# narvi-cpu.net
KiCad netlist of a schematic drawn in EAGLE
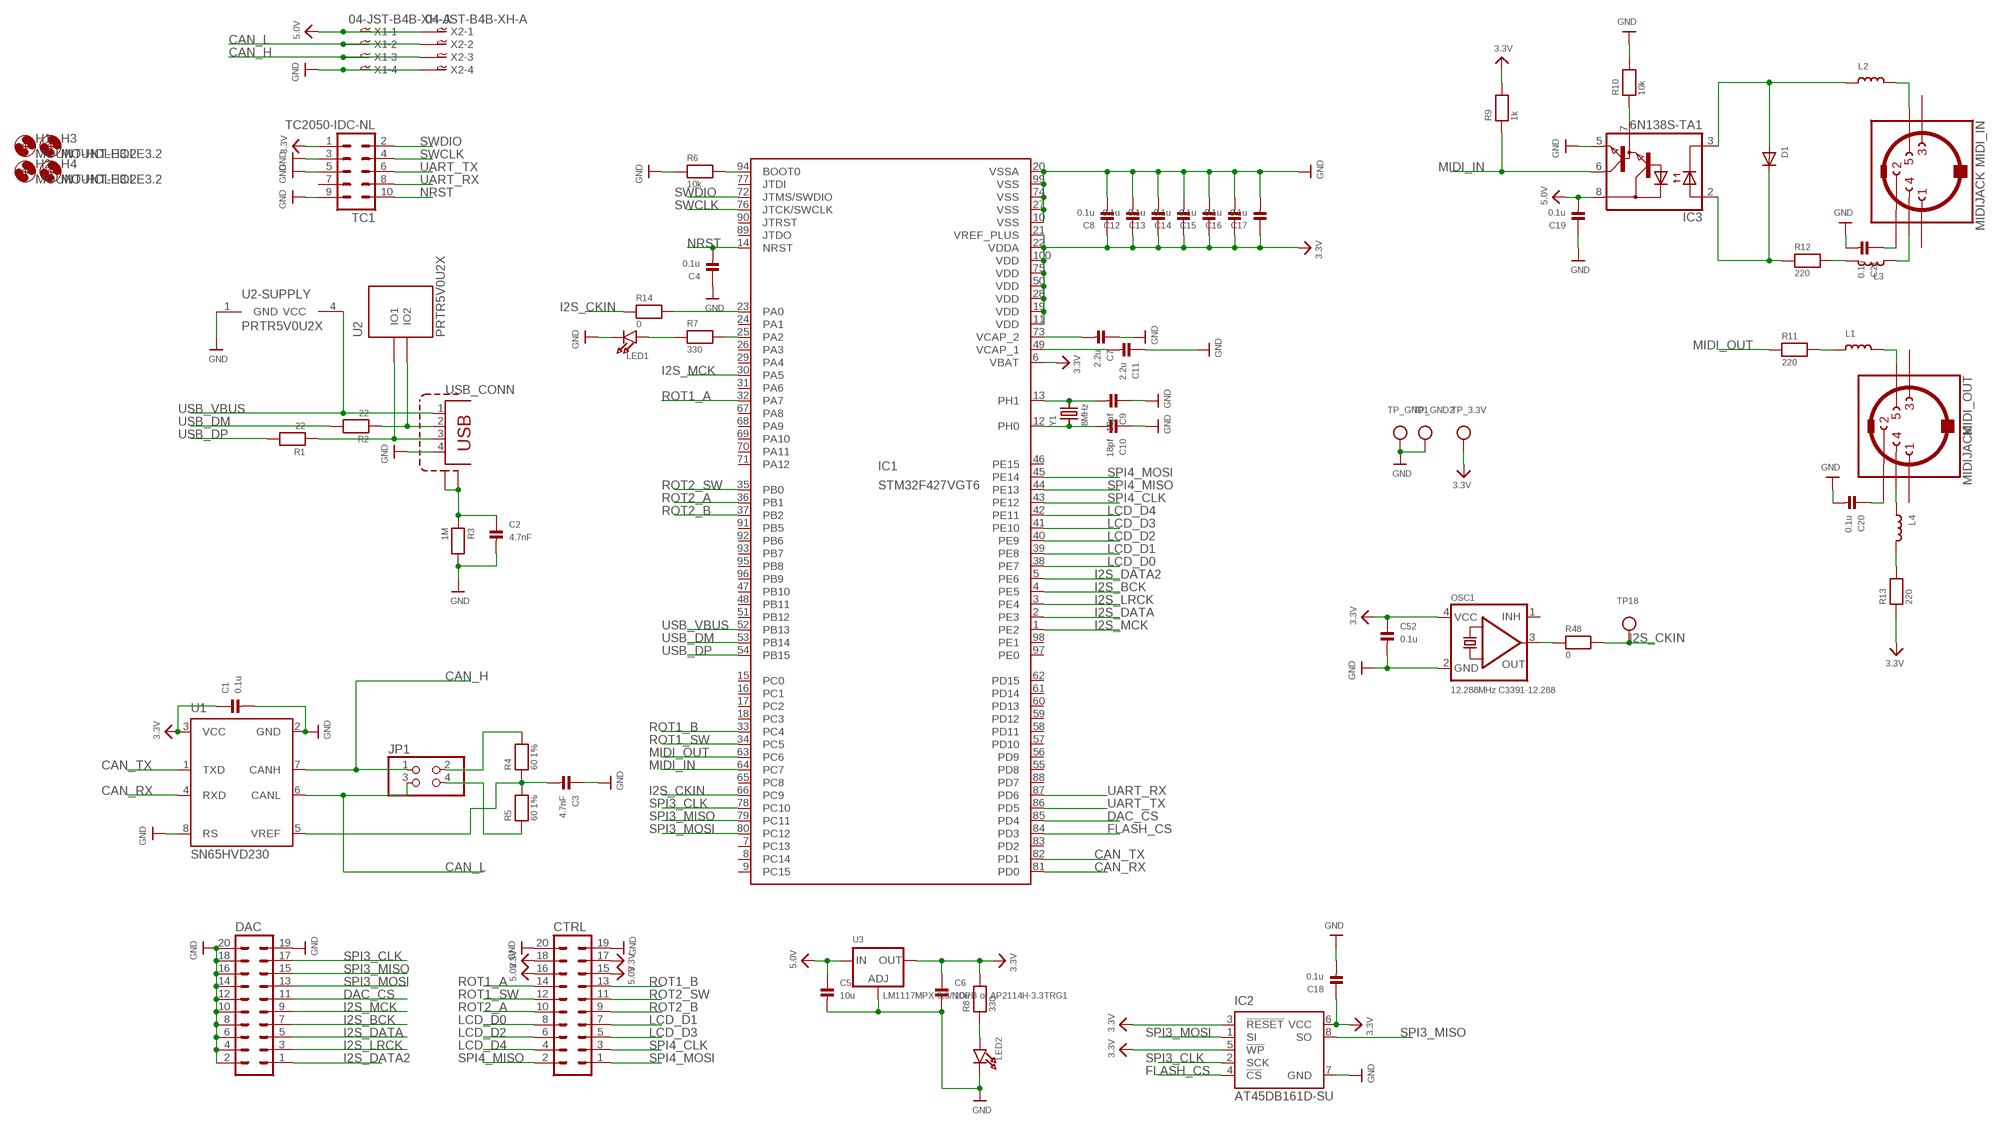
[diagram p0: schematic, sheet 1]

(export (version "E")
  (design (tool "Eeschema 10.0.6"))
  (components
    (comp (ref "C1")
      (value "0.1u")
      (footprint "eagle-import:0603")
      (fields (field (name "PARTNO") "0805DD104KAT2A"))
      (libsource (lib "eagle-import") (part "CAP_CERAMIC0603"))
    )
    (comp (ref "C2")
      (value "4.7nF")
      (footprint "eagle-import:0805")
      (fields (field (name "PARTNO") "885012207090"))
      (libsource (lib "eagle-import") (part "CAP_CERAMIC0805"))
    )
    (comp (ref "C3")
      (value "4.7nF")
      (footprint "eagle-import:0805")
      (fields (field (name "PARTNO") "885012207090"))
      (libsource (lib "eagle-import") (part "CAP_CERAMIC0805"))
    )
    (comp (ref "C4")
      (value "0.1u")
      (footprint "eagle-import:0603")
      (fields (field (name "PARTNO") "0805DD104KAT2A"))
      (libsource (lib "eagle-import") (part "CAP_CERAMIC0603"))
    )
    (comp (ref "C5")
      (value "10u")
      (footprint "eagle-import:0805")
      (fields (field (name "PARTNO") "81-GRM21BR6YA106KE3L"))
      (libsource (lib "eagle-import") (part "CAP_CERAMIC0805"))
    )
    (comp (ref "C6")
      (value "10u")
      (footprint "eagle-import:0805")
      (fields (field (name "PARTNO") "81-GRM21BR6YA106KE3L"))
      (libsource (lib "eagle-import") (part "CAP_CERAMIC0805"))
    )
    (comp (ref "C7")
      (value "2.2u")
      (footprint "eagle-import:0805")
      (fields (field (name "PARTNO") "581-08053D225MAT2A"))
      (libsource (lib "eagle-import") (part "CAP_CERAMIC0805"))
    )
    (comp (ref "C8")
      (value "0.1u")
      (footprint "eagle-import:0603")
      (fields (field (name "PARTNO") "0805DD104KAT2A"))
      (libsource (lib "eagle-import") (part "CAP_CERAMIC0603"))
    )
    (comp (ref "C9")
      (value "18pf")
      (footprint "eagle-import:0805")
      (fields (field (name "PARTNO") "C0805C180M3GACTU"))
      (libsource (lib "eagle-import") (part "CAP_CERAMIC0805"))
    )
    (comp (ref "C10")
      (value "18pf")
      (footprint "eagle-import:0805")
      (fields (field (name "PARTNO") "C0805C180M3GACTU"))
      (libsource (lib "eagle-import") (part "CAP_CERAMIC0805"))
    )
    (comp (ref "C11")
      (value "2.2u")
      (footprint "eagle-import:0805")
      (fields (field (name "PARTNO") "581-08053D225MAT2A"))
      (libsource (lib "eagle-import") (part "CAP_CERAMIC0805"))
    )
    (comp (ref "C12")
      (value "0.1u")
      (footprint "eagle-import:0603")
      (fields (field (name "PARTNO") "0805DD104KAT2A"))
      (libsource (lib "eagle-import") (part "CAP_CERAMIC0603"))
    )
    (comp (ref "C13")
      (value "0.1u")
      (footprint "eagle-import:0603")
      (fields (field (name "PARTNO") "0805DD104KAT2A"))
      (libsource (lib "eagle-import") (part "CAP_CERAMIC0603"))
    )
    (comp (ref "C14")
      (value "0.1u")
      (footprint "eagle-import:0603")
      (fields (field (name "PARTNO") "0805DD104KAT2A"))
      (libsource (lib "eagle-import") (part "CAP_CERAMIC0603"))
    )
    (comp (ref "C15")
      (value "0.1u")
      (footprint "eagle-import:0603")
      (fields (field (name "PARTNO") "0805DD104KAT2A"))
      (libsource (lib "eagle-import") (part "CAP_CERAMIC0603"))
    )
    (comp (ref "C16")
      (value "0.1u")
      (footprint "eagle-import:0603")
      (fields (field (name "PARTNO") "0805DD104KAT2A"))
      (libsource (lib "eagle-import") (part "CAP_CERAMIC0603"))
    )
    (comp (ref "C17")
      (value "0.1u")
      (footprint "eagle-import:0603")
      (fields (field (name "PARTNO") "0805DD104KAT2A"))
      (libsource (lib "eagle-import") (part "CAP_CERAMIC0603"))
    )
    (comp (ref "C18")
      (value "0.1u")
      (footprint "eagle-import:0603")
      (fields (field (name "PARTNO") "0805DD104KAT2A"))
      (libsource (lib "eagle-import") (part "CAP_CERAMIC0603"))
    )
    (comp (ref "C19")
      (value "0.1u")
      (footprint "eagle-import:0603")
      (fields (field (name "PARTNO") "0805DD104KAT2A"))
      (libsource (lib "eagle-import") (part "CAP_CERAMIC0603"))
    )
    (comp (ref "C20")
      (value "0.1u")
      (footprint "eagle-import:0603")
      (fields (field (name "PARTNO") "0805DD104KAT2A"))
      (libsource (lib "eagle-import") (part "CAP_CERAMIC0603"))
    )
    (comp (ref "C21")
      (value "0.1u")
      (footprint "eagle-import:0603")
      (fields (field (name "PARTNO") "0805DD104KAT2A"))
      (libsource (lib "eagle-import") (part "CAP_CERAMIC0603"))
    )
    (comp (ref "C52")
      (value "0.1u")
      (footprint "eagle-import:0603")
      (libsource (lib "eagle-import") (part "CAP_CERAMIC0603"))
    )
    (comp (ref "CTRL")
      (value "ML20")
      (footprint "eagle-import:ML20")
      (fields (field (name "PARTNO") "61202021621"))
      (libsource (lib "eagle-import") (part "ML20"))
    )
    (comp (ref "D1")
      (value "DIODESOD-123")
      (footprint "eagle-import:SOD-123")
      (fields (field (name "PARTNO") "MBR120"))
      (libsource (lib "eagle-import") (part "DIODESOD-123"))
    )
    (comp (ref "DAC")
      (value "ML20")
      (footprint "eagle-import:ML20")
      (fields (field (name "PARTNO") "61202021621"))
      (libsource (lib "eagle-import") (part "ML20"))
    )
    (comp (ref "H1")
      (value "MOUNT-HOLE3.2")
      (footprint "eagle-import:3,2")
      (libsource (lib "eagle-import") (part "MOUNT-HOLE3.2"))
    )
    (comp (ref "H2")
      (value "MOUNT-HOLE3.2")
      (footprint "eagle-import:3,2")
      (libsource (lib "eagle-import") (part "MOUNT-HOLE3.2"))
    )
    (comp (ref "H3")
      (value "MOUNT-HOLE3.2")
      (footprint "eagle-import:3,2")
      (libsource (lib "eagle-import") (part "MOUNT-HOLE3.2"))
    )
    (comp (ref "H4")
      (value "MOUNT-HOLE3.2")
      (footprint "eagle-import:3,2")
      (libsource (lib "eagle-import") (part "MOUNT-HOLE3.2"))
    )
    (comp (ref "IC1")
      (value "STM32F427VGT6")
      (footprint "eagle-import:TQFP100")
      (libsource (lib "eagle-import") (part "STM32F42X_43X_LQFP100"))
    )
    (comp (ref "IC2")
      (value "AT45DB161D-SU")
      (footprint "eagle-import:8S2")
      (fields (field (name "MF") "ATMEL"))
      (libsource (lib "eagle-import") (part "AT45DB161D-SU"))
    )
    (comp (ref "IC3")
      (value "6N138S-TA1")
      (footprint "eagle-import:SO8-GW300")
      (fields (field (name "PARTNO") "6N138S"))
      (libsource (lib "eagle-import") (part "6N138SMD"))
    )
    (comp (ref "JP1")
      (value "PINHD-2X2")
      (footprint "eagle-import:2X02")
      (fields (field (name "MPN") "5-146254-2"))
      (libsource (lib "eagle-import") (part "PINHD-2X2"))
    )
    (comp (ref "L1")
      (value "INDUCTOR0805")
      (footprint "eagle-import:0805")
      (fields (field (name "PARTNO") "70-ILHB0805ER601V"))
      (libsource (lib "eagle-import") (part "INDUCTOR0805"))
    )
    (comp (ref "L2")
      (value "INDUCTOR0805")
      (footprint "eagle-import:0805")
      (fields (field (name "PARTNO") "70-ILHB0805ER601V"))
      (libsource (lib "eagle-import") (part "INDUCTOR0805"))
    )
    (comp (ref "L3")
      (value "INDUCTOR0805")
      (footprint "eagle-import:0805")
      (fields (field (name "PARTNO") "70-ILHB0805ER601V"))
      (libsource (lib "eagle-import") (part "INDUCTOR0805"))
    )
    (comp (ref "L4")
      (value "INDUCTOR0805")
      (footprint "eagle-import:0805")
      (fields (field (name "PARTNO") "70-ILHB0805ER601V"))
      (libsource (lib "eagle-import") (part "INDUCTOR0805"))
    )
    (comp (ref "LED1")
      (value "LED0805")
      (footprint "eagle-import:CHIPLED_0805")
      (fields (field (name "PARTNO") "604-APT2012YC"))
      (libsource (lib "eagle-import") (part "LED0805"))
    )
    (comp (ref "LED2")
      (value "LED0805")
      (footprint "eagle-import:CHIPLED_0805")
      (fields (field (name "PARTNO") "604-APT2012YC"))
      (libsource (lib "eagle-import") (part "LED0805"))
    )
    (comp (ref "MIDI_IN")
      (value "MIDIJACK")
      (footprint "eagle-import:CP-2350")
      (libsource (lib "eagle-import") (part "MIDIJACK"))
    )
    (comp (ref "MIDI_OUT")
      (value "MIDIJACK")
      (footprint "eagle-import:CP-2350")
      (libsource (lib "eagle-import") (part "MIDIJACK"))
    )
    (comp (ref "OSC1")
      (value "12.288MHz C3391-12.288")
      (footprint "eagle-import:OSC_7X5MM")
      (libsource (lib "eagle-import") (part "OSCILLATOR"))
    )
    (comp (ref "R1")
      (value "22")
      (footprint "eagle-import:0805")
      (fields (field (name "MPN") "MF-RES-0603-22") (field (name "PARTNO") "ERJ-6ENF22R0V"))
      (libsource (lib "eagle-import") (part "RESISTOR0805"))
    )
    (comp (ref "R2")
      (value "22")
      (footprint "eagle-import:0805")
      (fields (field (name "MPN") "MF-RES-0603-22") (field (name "PARTNO") "ERJ-6ENF22R0V"))
      (libsource (lib "eagle-import") (part "RESISTOR0805"))
    )
    (comp (ref "R3")
      (value "1M")
      (footprint "eagle-import:0805")
      (fields (field (name "PARTNO") "AS08J1004ET"))
      (libsource (lib "eagle-import") (part "RESISTOR0805"))
    )
    (comp (ref "R4")
      (value "60 1%")
      (footprint "eagle-import:0805")
      (fields (field (name "MPN") "MF-RES-0603-60.4") (field (name "PARTNO") "ERJ-6ENF60R4V"))
      (libsource (lib "eagle-import") (part "RESISTOR0805"))
    )
    (comp (ref "R5")
      (value "60 1%")
      (footprint "eagle-import:0805")
      (fields (field (name "MPN") "MF-RES-0603-60.4") (field (name "PARTNO") "ERJ-6ENF60R4V"))
      (libsource (lib "eagle-import") (part "RESISTOR0805"))
    )
    (comp (ref "R6")
      (value "10k")
      (footprint "eagle-import:0805")
      (fields (field (name "PARTNO") "RC0805FR-0710KL"))
      (libsource (lib "eagle-import") (part "RESISTOR0805"))
    )
    (comp (ref "R7")
      (value "330")
      (footprint "eagle-import:0805")
      (fields (field (name "MPN") "MF-RES-0603-330") (field (name "PARTNO") "CPF0805B330RE1"))
      (libsource (lib "eagle-import") (part "RESISTOR0805"))
    )
    (comp (ref "R8")
      (value "330")
      (footprint "eagle-import:0805")
      (fields (field (name "MPN") "MF-RES-0603-330") (field (name "PARTNO") "CPF0805B330RE1"))
      (libsource (lib "eagle-import") (part "RESISTOR0805"))
    )
    (comp (ref "R9")
      (value "1k")
      (footprint "eagle-import:0805")
      (fields (field (name "PARTNO") "AS08J1001ET"))
      (libsource (lib "eagle-import") (part "RESISTOR0805"))
    )
    (comp (ref "R10")
      (value "10k")
      (footprint "eagle-import:0805")
      (fields (field (name "PARTNO") "RC0805FR-0710KL"))
      (libsource (lib "eagle-import") (part "RESISTOR0805"))
    )
    (comp (ref "R11")
      (value "220")
      (footprint "eagle-import:0805")
      (fields (field (name "PARTNO") "ERJ-6GEYJ221V"))
      (libsource (lib "eagle-import") (part "RESISTOR0805"))
    )
    (comp (ref "R12")
      (value "220")
      (footprint "eagle-import:0805")
      (fields (field (name "PARTNO") "ERJ-6GEYJ221V"))
      (libsource (lib "eagle-import") (part "RESISTOR0805"))
    )
    (comp (ref "R13")
      (value "220")
      (footprint "eagle-import:0805")
      (fields (field (name "PARTNO") "ERJ-6GEYJ221V"))
      (libsource (lib "eagle-import") (part "RESISTOR0805"))
    )
    (comp (ref "R14")
      (value "0")
      (footprint "eagle-import:0805")
      (fields (field (name "MPN") "MF-RES-0603-330") (field (name "PARTNO") "CPF0805B330RE1"))
      (libsource (lib "eagle-import") (part "RESISTOR0805"))
    )
    (comp (ref "R48")
      (value "0")
      (footprint "eagle-import:_0805")
      (libsource (lib "eagle-import") (part "RESISTOR_0805"))
    )
    (comp (ref "TC1")
      (value "TC2050-IDC-NL")
      (footprint "eagle-import:TC2050-IDC-NL")
      (libsource (lib "eagle-import") (part "TC2050-IDC-NL"))
    )
    (comp (ref "TP18")
      (value "TESTPOINT0.1\"")
      (footprint "eagle-import:1X01_ROUND")
      (libsource (lib "eagle-import") (part "TESTPOINT0.1{dblquote}"))
    )
    (comp (ref "TP_3.3V")
      (value "TESTPOINT0.1\"")
      (footprint "eagle-import:1X01_ROUND")
      (libsource (lib "eagle-import") (part "TESTPOINT0.1{dblquote}"))
    )
    (comp (ref "TP_GND1")
      (value "TESTPOINT0.1\"")
      (footprint "eagle-import:1X01_ROUND")
      (libsource (lib "eagle-import") (part "TESTPOINT0.1{dblquote}"))
    )
    (comp (ref "TP_GND2")
      (value "TESTPOINT0.1\"")
      (footprint "eagle-import:1X01_ROUND")
      (libsource (lib "eagle-import") (part "TESTPOINT0.1{dblquote}"))
    )
    (comp (ref "U1")
      (value "SN65HVD230")
      (footprint "eagle-import:SO8")
      (fields (field (name "MPN") "SN65HVD230DR"))
      (libsource (lib "eagle-import") (part "SN65HVD230"))
    )
    (comp (ref "U2")
      (value "PRTR5V0U2X")
      (footprint "eagle-import:SOT-143B")
      (fields (field (name "MANUFACTURER") "NXP Semiconductors") (field (name "MPN") "PRTR5V0U2X,215"))
      (libsource (lib "eagle-import") (part "PRTR5V0U2X?"))
    )
    (comp (ref "U3")
      (value "LM1117MPX-3.3/NOPB or AP2114H-3.3TRG1")
      (footprint "eagle-import:SOT223-R")
      (fields (field (name "MPN") "LM1117MPX-3.3/NOPB"))
      (libsource (lib "eagle-import") (part "LM1117SOT223-REFLOW"))
    )
    (comp (ref "USB")
      (value "TE-292304-1")
      (footprint "eagle-import:TE-292304-1")
      (fields (field (name "MPN") "292304-1 ") (field (name "POPULATE") "0"))
      (libsource (lib "eagle-import") (part "TE-292304-1"))
    )
    (comp (ref "X1")
      (value "04-JST-B4B-XH-A")
      (footprint "eagle-import:B4B-XH")
      (fields (field (name "MPN") "B4B-XH-A(LF)(SN)"))
      (libsource (lib "eagle-import") (part "04-JST-B4B-XH-A"))
    )
    (comp (ref "X2")
      (value "04-JST-B4B-XH-A")
      (footprint "eagle-import:B4B-XH")
      (fields (field (name "MPN") "B4B-XH-A(LF)(SN)"))
      (libsource (lib "eagle-import") (part "04-JST-B4B-XH-A"))
    )
    (comp (ref "Y1")
      (value "8MHz")
      (footprint "eagle-import:HC49UP")
      (fields (field (name "PARTNO") "ABLS2-8.000MHz-B1U-T"))
      (libsource (lib "eagle-import") (part "CRYSTALSMD"))
    )
  )
  (nets
    (net (code "1") (name "/CAN_H") (class "Default")
      (node (ref "JP1") (pin "1") (pinfunction "1_1") (pintype "passive"))
      (node (ref "U1") (pin "7") (pinfunction "CANH_7") (pintype "bidirectional"))
      (node (ref "X1") (pin "P$3") (pinfunction "1_P$3") (pintype "passive"))
      (node (ref "X2") (pin "P$3") (pinfunction "1_P$3") (pintype "passive"))
    )
    (net (code "2") (name "/CAN_L") (class "Default")
      (node (ref "JP1") (pin "3") (pinfunction "3_3") (pintype "passive"))
      (node (ref "U1") (pin "6") (pinfunction "CANL_6") (pintype "bidirectional"))
      (node (ref "X1") (pin "P$2") (pinfunction "1_P$2") (pintype "passive"))
      (node (ref "X2") (pin "P$2") (pinfunction "1_P$2") (pintype "passive"))
    )
    (net (code "3") (name "/CAN_RX") (class "Default")
      (node (ref "IC1") (pin "81") (pinfunction "PD0_81") (pintype "bidirectional"))
      (node (ref "U1") (pin "4") (pinfunction "RXD_4") (pintype "output"))
    )
    (net (code "4") (name "/CAN_TX") (class "Default")
      (node (ref "IC1") (pin "82") (pinfunction "PD1_82") (pintype "bidirectional"))
      (node (ref "U1") (pin "1") (pinfunction "TXD_1") (pintype "input"))
    )
    (net (code "5") (name "/DAC_CS") (class "Default")
      (node (ref "DAC") (pin "11") (pinfunction "11_11") (pintype "passive"))
      (node (ref "IC1") (pin "85") (pinfunction "PD4_85") (pintype "bidirectional"))
    )
    (net (code "6") (name "/FLASH_CS") (class "Default")
      (node (ref "IC1") (pin "84") (pinfunction "PD3_84") (pintype "bidirectional"))
      (node (ref "IC2") (pin "4") (pinfunction "~{CS}_4") (pintype "input"))
    )
    (net (code "7") (name "/I2S_BCK") (class "Default")
      (node (ref "DAC") (pin "7") (pinfunction "7_7") (pintype "passive"))
      (node (ref "IC1") (pin "4") (pinfunction "PE5_4") (pintype "bidirectional"))
    )
    (net (code "8") (name "/I2S_CKIN") (class "Default")
      (node (ref "IC1") (pin "66") (pinfunction "PC9_66") (pintype "bidirectional"))
      (node (ref "R14") (pin "1") (pinfunction "1_1") (pintype "passive"))
      (node (ref "R48") (pin "2") (pinfunction "2_2") (pintype "passive"))
      (node (ref "TP18") (pin "1") (pinfunction "P$1_1") (pintype "bidirectional"))
    )
    (net (code "9") (name "/I2S_DATA") (class "Default")
      (node (ref "DAC") (pin "5") (pinfunction "5_5") (pintype "passive"))
      (node (ref "IC1") (pin "2") (pinfunction "PE3_2") (pintype "bidirectional"))
    )
    (net (code "10") (name "/I2S_DATA2") (class "Default")
      (node (ref "DAC") (pin "1") (pinfunction "1_1") (pintype "passive"))
      (node (ref "IC1") (pin "5") (pinfunction "PE6_5") (pintype "bidirectional"))
    )
    (net (code "11") (name "/I2S_LRCK") (class "Default")
      (node (ref "DAC") (pin "3") (pinfunction "3_3") (pintype "passive"))
      (node (ref "IC1") (pin "3") (pinfunction "PE4_3") (pintype "bidirectional"))
    )
    (net (code "12") (name "/I2S_MCK") (class "Default")
      (node (ref "DAC") (pin "9") (pinfunction "9_9") (pintype "passive"))
      (node (ref "IC1") (pin "1") (pinfunction "PE2_1") (pintype "bidirectional"))
      (node (ref "IC1") (pin "30") (pinfunction "PA5_30") (pintype "bidirectional"))
    )
    (net (code "13") (name "/LCD_D0") (class "Default")
      (node (ref "CTRL") (pin "8") (pinfunction "8_8") (pintype "passive"))
      (node (ref "IC1") (pin "38") (pinfunction "PE7_38") (pintype "bidirectional"))
    )
    (net (code "14") (name "/LCD_D1") (class "Default")
      (node (ref "CTRL") (pin "7") (pinfunction "7_7") (pintype "passive"))
      (node (ref "IC1") (pin "39") (pinfunction "PE8_39") (pintype "bidirectional"))
    )
    (net (code "15") (name "/LCD_D2") (class "Default")
      (node (ref "CTRL") (pin "6") (pinfunction "6_6") (pintype "passive"))
      (node (ref "IC1") (pin "40") (pinfunction "PE9_40") (pintype "bidirectional"))
    )
    (net (code "16") (name "/LCD_D3") (class "Default")
      (node (ref "CTRL") (pin "5") (pinfunction "5_5") (pintype "passive"))
      (node (ref "IC1") (pin "41") (pinfunction "PE10_41") (pintype "bidirectional"))
    )
    (net (code "17") (name "/LCD_D4") (class "Default")
      (node (ref "CTRL") (pin "4") (pinfunction "4_4") (pintype "passive"))
      (node (ref "IC1") (pin "42") (pinfunction "PE11_42") (pintype "bidirectional"))
    )
    (net (code "18") (name "/MIDI_IN") (class "Default")
      (node (ref "IC1") (pin "64") (pinfunction "PC7_64") (pintype "bidirectional"))
      (node (ref "IC3") (pin "6") (pinfunction "VO_6") (pintype "passive"))
      (node (ref "R9") (pin "1") (pinfunction "1_1") (pintype "passive"))
    )
    (net (code "19") (name "/MIDI_OUT") (class "Default")
      (node (ref "IC1") (pin "63") (pinfunction "PC6_63") (pintype "bidirectional"))
      (node (ref "R11") (pin "1") (pinfunction "1_1") (pintype "passive"))
    )
    (net (code "20") (name "/NRST") (class "Default")
      (node (ref "C4") (pin "2") (pinfunction "P$2_2") (pintype "passive"))
      (node (ref "IC1") (pin "14") (pinfunction "NRST_14") (pintype "input"))
      (node (ref "TC1") (pin "10") (pinfunction "10_10") (pintype "passive"))
    )
    (net (code "21") (name "/ROT1_A") (class "Default")
      (node (ref "CTRL") (pin "14") (pinfunction "14_14") (pintype "passive"))
      (node (ref "IC1") (pin "32") (pinfunction "PA7_32") (pintype "bidirectional"))
    )
    (net (code "22") (name "/ROT1_B") (class "Default")
      (node (ref "CTRL") (pin "13") (pinfunction "13_13") (pintype "passive"))
      (node (ref "IC1") (pin "33") (pinfunction "PC4_33") (pintype "bidirectional"))
    )
    (net (code "23") (name "/ROT1_SW") (class "Default")
      (node (ref "CTRL") (pin "12") (pinfunction "12_12") (pintype "passive"))
      (node (ref "IC1") (pin "34") (pinfunction "PC5_34") (pintype "bidirectional"))
    )
    (net (code "24") (name "/ROT2_A") (class "Default")
      (node (ref "CTRL") (pin "10") (pinfunction "10_10") (pintype "passive"))
      (node (ref "IC1") (pin "36") (pinfunction "PB1_36") (pintype "bidirectional"))
    )
    (net (code "25") (name "/ROT2_B") (class "Default")
      (node (ref "CTRL") (pin "9") (pinfunction "9_9") (pintype "passive"))
      (node (ref "IC1") (pin "37") (pinfunction "PB2_37") (pintype "bidirectional"))
    )
    (net (code "26") (name "/ROT2_SW") (class "Default")
      (node (ref "CTRL") (pin "11") (pinfunction "11_11") (pintype "passive"))
      (node (ref "IC1") (pin "35") (pinfunction "PB0_35") (pintype "bidirectional"))
    )
    (net (code "27") (name "/SPI3_CLK") (class "Default")
      (node (ref "DAC") (pin "17") (pinfunction "17_17") (pintype "passive"))
      (node (ref "IC1") (pin "78") (pinfunction "PC10_78") (pintype "bidirectional"))
      (node (ref "IC2") (pin "2") (pinfunction "SCK_2") (pintype "input"))
    )
    (net (code "28") (name "/SPI3_MISO") (class "Default")
      (node (ref "DAC") (pin "15") (pinfunction "15_15") (pintype "passive"))
      (node (ref "IC1") (pin "79") (pinfunction "PC11_79") (pintype "bidirectional"))
      (node (ref "IC2") (pin "8") (pinfunction "SO_8") (pintype "output"))
    )
    (net (code "29") (name "/SPI3_MOSI") (class "Default")
      (node (ref "DAC") (pin "13") (pinfunction "13_13") (pintype "passive"))
      (node (ref "IC1") (pin "80") (pinfunction "PC12_80") (pintype "bidirectional"))
      (node (ref "IC2") (pin "1") (pinfunction "SI_1") (pintype "input"))
    )
    (net (code "30") (name "/SPI4_CLK") (class "Default")
      (node (ref "CTRL") (pin "3") (pinfunction "3_3") (pintype "passive"))
      (node (ref "IC1") (pin "43") (pinfunction "PE12_43") (pintype "bidirectional"))
    )
    (net (code "31") (name "/SPI4_MISO") (class "Default")
      (node (ref "CTRL") (pin "2") (pinfunction "2_2") (pintype "passive"))
      (node (ref "IC1") (pin "44") (pinfunction "PE13_44") (pintype "bidirectional"))
    )
    (net (code "32") (name "/SPI4_MOSI") (class "Default")
      (node (ref "CTRL") (pin "1") (pinfunction "1_1") (pintype "passive"))
      (node (ref "IC1") (pin "45") (pinfunction "PE14_45") (pintype "bidirectional"))
    )
    (net (code "33") (name "/SWCLK") (class "Default")
      (node (ref "IC1") (pin "76") (pinfunction "JTCK/SWCLK_76") (pintype "input"))
      (node (ref "TC1") (pin "4") (pinfunction "4_4") (pintype "passive"))
    )
    (net (code "34") (name "/SWDIO") (class "Default")
      (node (ref "IC1") (pin "72") (pinfunction "JTMS/SWDIO_72") (pintype "input"))
      (node (ref "TC1") (pin "2") (pinfunction "2_2") (pintype "passive"))
    )
    (net (code "35") (name "/UART_RX") (class "Default")
      (node (ref "IC1") (pin "87") (pinfunction "PD6_87") (pintype "bidirectional"))
      (node (ref "TC1") (pin "8") (pinfunction "8_8") (pintype "passive"))
    )
    (net (code "36") (name "/UART_TX") (class "Default")
      (node (ref "IC1") (pin "86") (pinfunction "PD5_86") (pintype "bidirectional"))
      (node (ref "TC1") (pin "6") (pinfunction "6_6") (pintype "passive"))
    )
    (net (code "37") (name "/USB_DM") (class "Default")
      (node (ref "IC1") (pin "53") (pinfunction "PB14_53") (pintype "bidirectional"))
      (node (ref "R2") (pin "2") (pinfunction "2_2") (pintype "passive"))
    )
    (net (code "38") (name "/USB_DP") (class "Default")
      (node (ref "IC1") (pin "54") (pinfunction "PB15_54") (pintype "bidirectional"))
      (node (ref "R1") (pin "2") (pinfunction "2_2") (pintype "passive"))
    )
    (net (code "39") (name "/USB_VBUS") (class "Default")
      (node (ref "IC1") (pin "52") (pinfunction "PB13_52") (pintype "bidirectional"))
      (node (ref "U2") (pin "4") (pinfunction "VCC_4") (pintype "bidirectional"))
      (node (ref "USB") (pin "1") (pinfunction "1_1") (pintype "bidirectional"))
    )
    (net (code "40") (name "3.3V") (class "Default")
      (node (ref "C1") (pin "1") (pinfunction "P$1_1") (pintype "passive"))
      (node (ref "C12") (pin "1") (pinfunction "P$1_1") (pintype "passive"))
      (node (ref "C13") (pin "1") (pinfunction "P$1_1") (pintype "passive"))
      (node (ref "C14") (pin "1") (pinfunction "P$1_1") (pintype "passive"))
      (node (ref "C15") (pin "1") (pinfunction "P$1_1") (pintype "passive"))
      (node (ref "C16") (pin "1") (pinfunction "P$1_1") (pintype "passive"))
      (node (ref "C17") (pin "1") (pinfunction "P$1_1") (pintype "passive"))
      (node (ref "C18") (pin "1") (pinfunction "P$1_1") (pintype "passive"))
      (node (ref "C52") (pin "1") (pinfunction "P$1_1") (pintype "passive"))
      (node (ref "C6") (pin "1") (pinfunction "P$1_1") (pintype "passive"))
      (node (ref "C8") (pin "1") (pinfunction "P$1_1") (pintype "passive"))
      (node (ref "CTRL") (pin "17") (pinfunction "17_17") (pintype "passive"))
      (node (ref "CTRL") (pin "18") (pinfunction "18_18") (pintype "passive"))
      (node (ref "IC1") (pin "100") (pinfunction "VDD_100") (pintype "power_in"))
      (node (ref "IC1") (pin "11") (pinfunction "VDD_11") (pintype "power_in"))
      (node (ref "IC1") (pin "19") (pinfunction "VDD_19") (pintype "power_in"))
      (node (ref "IC1") (pin "21") (pinfunction "VREF_PLUS_21") (pintype "passive"))
      (node (ref "IC1") (pin "22") (pinfunction "VDDA_22") (pintype "power_in"))
      (node (ref "IC1") (pin "28") (pinfunction "VDD_28") (pintype "power_in"))
      (node (ref "IC1") (pin "50") (pinfunction "VDD_50") (pintype "power_in"))
      (node (ref "IC1") (pin "6") (pinfunction "VBAT_6") (pintype "passive"))
      (node (ref "IC1") (pin "75") (pinfunction "VDD_75") (pintype "power_in"))
      (node (ref "IC2") (pin "3") (pinfunction "~{RESET}_3") (pintype "input"))
      (node (ref "IC2") (pin "5") (pinfunction "~{WP}_5") (pintype "input"))
      (node (ref "IC2") (pin "6") (pinfunction "VCC_6") (pintype "power_in"))
      (node (ref "OSC1") (pin "4") (pinfunction "VCC_4") (pintype "power_in"))
      (node (ref "R13") (pin "1") (pinfunction "1_1") (pintype "passive"))
      (node (ref "R8") (pin "2") (pinfunction "2_2") (pintype "passive"))
      (node (ref "R9") (pin "2") (pinfunction "2_2") (pintype "passive"))
      (node (ref "TC1") (pin "1") (pinfunction "1_1") (pintype "passive"))
      (node (ref "TP_3.3V") (pin "1") (pinfunction "P$1_1") (pintype "bidirectional"))
      (node (ref "U1") (pin "3") (pinfunction "VCC_3") (pintype "power_in"))
      (node (ref "U3") (pin "2") (pinfunction "OUT_2") (pintype "passive"))
    )
    (net (code "41") (name "5.0V") (class "Default")
      (node (ref "C19") (pin "2") (pinfunction "P$2_2") (pintype "passive"))
      (node (ref "C5") (pin "1") (pinfunction "P$1_1") (pintype "passive"))
      (node (ref "CTRL") (pin "15") (pinfunction "15_15") (pintype "passive"))
      (node (ref "CTRL") (pin "16") (pinfunction "16_16") (pintype "passive"))
      (node (ref "IC3") (pin "8") (pinfunction "VCC_8") (pintype "passive"))
      (node (ref "U3") (pin "3") (pinfunction "IN_3") (pintype "input"))
      (node (ref "X1") (pin "P$1") (pinfunction "1_P$1") (pintype "passive"))
      (node (ref "X2") (pin "P$1") (pinfunction "1_P$1") (pintype "passive"))
    )
    (net (code "42") (name "GND") (class "Default")
      (node (ref "C1") (pin "2") (pinfunction "P$2_2") (pintype "passive"))
      (node (ref "C10") (pin "1") (pinfunction "P$1_1") (pintype "passive"))
      (node (ref "C11") (pin "1") (pinfunction "P$1_1") (pintype "passive"))
      (node (ref "C12") (pin "2") (pinfunction "P$2_2") (pintype "passive"))
      (node (ref "C13") (pin "2") (pinfunction "P$2_2") (pintype "passive"))
      (node (ref "C14") (pin "2") (pinfunction "P$2_2") (pintype "passive"))
      (node (ref "C15") (pin "2") (pinfunction "P$2_2") (pintype "passive"))
      (node (ref "C16") (pin "2") (pinfunction "P$2_2") (pintype "passive"))
      (node (ref "C17") (pin "2") (pinfunction "P$2_2") (pintype "passive"))
      (node (ref "C18") (pin "2") (pinfunction "P$2_2") (pintype "passive"))
      (node (ref "C19") (pin "1") (pinfunction "P$1_1") (pintype "passive"))
      (node (ref "C2") (pin "2") (pinfunction "P$2_2") (pintype "passive"))
      (node (ref "C20") (pin "2") (pinfunction "P$2_2") (pintype "passive"))
      (node (ref "C21") (pin "2") (pinfunction "P$2_2") (pintype "passive"))
      (node (ref "C3") (pin "1") (pinfunction "P$1_1") (pintype "passive"))
      (node (ref "C4") (pin "1") (pinfunction "P$1_1") (pintype "passive"))
      (node (ref "C5") (pin "2") (pinfunction "P$2_2") (pintype "passive"))
      (node (ref "C52") (pin "2") (pinfunction "P$2_2") (pintype "passive"))
      (node (ref "C6") (pin "2") (pinfunction "P$2_2") (pintype "passive"))
      (node (ref "C7") (pin "1") (pinfunction "P$1_1") (pintype "passive"))
      (node (ref "C8") (pin "2") (pinfunction "P$2_2") (pintype "passive"))
      (node (ref "C9") (pin "1") (pinfunction "P$1_1") (pintype "passive"))
      (node (ref "CTRL") (pin "19") (pinfunction "19_19") (pintype "passive"))
      (node (ref "CTRL") (pin "20") (pinfunction "20_20") (pintype "passive"))
      (node (ref "DAC") (pin "10") (pinfunction "10_10") (pintype "passive"))
      (node (ref "DAC") (pin "12") (pinfunction "12_12") (pintype "passive"))
      (node (ref "DAC") (pin "14") (pinfunction "14_14") (pintype "passive"))
      (node (ref "DAC") (pin "16") (pinfunction "16_16") (pintype "passive"))
      (node (ref "DAC") (pin "18") (pinfunction "18_18") (pintype "passive"))
      (node (ref "DAC") (pin "19") (pinfunction "19_19") (pintype "passive"))
      (node (ref "DAC") (pin "2") (pinfunction "2_2") (pintype "passive"))
      (node (ref "DAC") (pin "20") (pinfunction "20_20") (pintype "passive"))
      (node (ref "DAC") (pin "4") (pinfunction "4_4") (pintype "passive"))
      (node (ref "DAC") (pin "6") (pinfunction "6_6") (pintype "passive"))
      (node (ref "DAC") (pin "8") (pinfunction "8_8") (pintype "passive"))
      (node (ref "IC1") (pin "10") (pinfunction "VSS_10") (pintype "power_in"))
      (node (ref "IC1") (pin "20") (pinfunction "VSSA_20") (pintype "power_in"))
      (node (ref "IC1") (pin "27") (pinfunction "VSS_27") (pintype "power_in"))
      (node (ref "IC1") (pin "74") (pinfunction "VSS_74") (pintype "power_in"))
      (node (ref "IC1") (pin "99") (pinfunction "VSS_99") (pintype "power_in"))
      (node (ref "IC2") (pin "7") (pinfunction "GND_7") (pintype "power_in"))
      (node (ref "IC3") (pin "5") (pinfunction "GND_5") (pintype "passive"))
      (node (ref "LED1") (pin "C") (pinfunction "C_C") (pintype "passive"))
      (node (ref "LED2") (pin "C") (pinfunction "C_C") (pintype "passive"))
      (node (ref "OSC1") (pin "2") (pinfunction "GND_2") (pintype "power_in"))
      (node (ref "R10") (pin "2") (pinfunction "2_2") (pintype "passive"))
      (node (ref "R3") (pin "2") (pinfunction "2_2") (pintype "passive"))
      (node (ref "R6") (pin "1") (pinfunction "1_1") (pintype "passive"))
      (node (ref "TC1") (pin "3") (pinfunction "3_3") (pintype "passive"))
      (node (ref "TC1") (pin "5") (pinfunction "5_5") (pintype "passive"))
      (node (ref "TC1") (pin "9") (pinfunction "9_9") (pintype "passive"))
      (node (ref "TP_GND1") (pin "1") (pinfunction "P$1_1") (pintype "bidirectional"))
      (node (ref "TP_GND2") (pin "1") (pinfunction "P$1_1") (pintype "bidirectional"))
      (node (ref "U1") (pin "2") (pinfunction "GND_2") (pintype "power_in"))
      (node (ref "U1") (pin "8") (pinfunction "RS_8") (pintype "input"))
      (node (ref "U2") (pin "1") (pinfunction "GND_1") (pintype "bidirectional"))
      (node (ref "U3") (pin "1") (pinfunction "ADJ_1") (pintype "input"))
      (node (ref "USB") (pin "4") (pinfunction "4_4") (pintype "bidirectional"))
      (node (ref "X1") (pin "P$4") (pinfunction "1_P$4") (pintype "passive"))
      (node (ref "X2") (pin "P$4") (pinfunction "1_P$4") (pintype "passive"))
    )
    (net (code "43") (name "Net-(C2-P$1)") (class "Default")
      (node (ref "C2") (pin "1") (pinfunction "P$1_1") (pintype "passive"))
      (node (ref "R3") (pin "1") (pinfunction "1_1") (pintype "passive"))
      (node (ref "USB") (pin "P$1") (pinfunction "S1_P$1") (pintype "passive"))
      (node (ref "USB") (pin "P$2") (pinfunction "S2_P$2") (pintype "passive"))
    )
    (net (code "44") (name "Net-(C3-P$2)") (class "Default")
      (node (ref "C3") (pin "2") (pinfunction "P$2_2") (pintype "passive"))
      (node (ref "R4") (pin "1") (pinfunction "1_1") (pintype "passive"))
      (node (ref "R5") (pin "2") (pinfunction "2_2") (pintype "passive"))
      (node (ref "U1") (pin "5") (pinfunction "VREF_5") (pintype "output"))
    )
    (net (code "45") (name "Net-(C7-P$2)") (class "Default")
      (node (ref "C7") (pin "2") (pinfunction "P$2_2") (pintype "passive"))
      (node (ref "IC1") (pin "73") (pinfunction "VCAP_2_73") (pintype "passive"))
    )
    (net (code "46") (name "Net-(C9-P$2)") (class "Default")
      (node (ref "C9") (pin "2") (pinfunction "P$2_2") (pintype "passive"))
      (node (ref "IC1") (pin "13") (pinfunction "PH1_13") (pintype "bidirectional"))
      (node (ref "Y1") (pin "2") (pinfunction "2_2") (pintype "passive"))
    )
    (net (code "47") (name "Net-(C10-P$2)") (class "Default")
      (node (ref "C10") (pin "2") (pinfunction "P$2_2") (pintype "passive"))
      (node (ref "IC1") (pin "12") (pinfunction "PH0_12") (pintype "bidirectional"))
      (node (ref "Y1") (pin "1") (pinfunction "1_1") (pintype "passive"))
    )
    (net (code "48") (name "Net-(C11-P$2)") (class "Default")
      (node (ref "C11") (pin "2") (pinfunction "P$2_2") (pintype "passive"))
      (node (ref "IC1") (pin "49") (pinfunction "VCAP_1_49") (pintype "passive"))
    )
    (net (code "49") (name "Net-(C20-P$1)") (class "Default")
      (node (ref "C20") (pin "1") (pinfunction "P$1_1") (pintype "passive"))
      (node (ref "MIDI_OUT") (pin "2") (pinfunction "2_2") (pintype "passive"))
    )
    (net (code "50") (name "Net-(C21-P$1)") (class "Default")
      (node (ref "C21") (pin "1") (pinfunction "P$1_1") (pintype "passive"))
      (node (ref "MIDI_IN") (pin "2") (pinfunction "2_2") (pintype "passive"))
    )
    (net (code "51") (name "Net-(IC1-BOOT0)") (class "Default")
      (node (ref "IC1") (pin "94") (pinfunction "BOOT0_94") (pintype "input"))
      (node (ref "R6") (pin "2") (pinfunction "2_2") (pintype "passive"))
    )
    (net (code "52") (name "Net-(IC1-PA0)") (class "Default")
      (node (ref "IC1") (pin "23") (pinfunction "PA0_23") (pintype "bidirectional"))
      (node (ref "R14") (pin "2") (pinfunction "2_2") (pintype "passive"))
    )
    (net (code "53") (name "Net-(IC1-PA2)") (class "Default")
      (node (ref "IC1") (pin "25") (pinfunction "PA2_25") (pintype "bidirectional"))
      (node (ref "R7") (pin "2") (pinfunction "2_2") (pintype "passive"))
    )
    (net (code "54") (name "Net-(IC3-A)") (class "Default")
      (node (ref "D1") (pin "C") (pinfunction "C_C") (pintype "passive"))
      (node (ref "IC3") (pin "2") (pinfunction "A_2") (pintype "passive"))
      (node (ref "R12") (pin "1") (pinfunction "1_1") (pintype "passive"))
    )
    (net (code "55") (name "Net-(IC3-C)") (class "Default")
      (node (ref "D1") (pin "A") (pinfunction "A_A") (pintype "passive"))
      (node (ref "IC3") (pin "3") (pinfunction "C_3") (pintype "passive"))
      (node (ref "L2") (pin "1") (pinfunction "1_1") (pintype "passive"))
    )
    (net (code "56") (name "Net-(IC3-VB)") (class "Default")
      (node (ref "IC3") (pin "7") (pinfunction "VB_7") (pintype "passive"))
      (node (ref "R10") (pin "1") (pinfunction "1_1") (pintype "passive"))
    )
    (net (code "57") (name "Net-(JP1-Pad2)") (class "Default")
      (node (ref "JP1") (pin "2") (pinfunction "2_2") (pintype "passive"))
      (node (ref "R4") (pin "2") (pinfunction "2_2") (pintype "passive"))
    )
    (net (code "58") (name "Net-(JP1-Pad4)") (class "Default")
      (node (ref "JP1") (pin "4") (pinfunction "4_4") (pintype "passive"))
      (node (ref "R5") (pin "1") (pinfunction "1_1") (pintype "passive"))
    )
    (net (code "59") (name "Net-(L1-Pad1)") (class "Default")
      (node (ref "L1") (pin "1") (pinfunction "1_1") (pintype "passive"))
      (node (ref "R11") (pin "2") (pinfunction "2_2") (pintype "passive"))
    )
    (net (code "60") (name "Net-(L1-Pad2)") (class "Default")
      (node (ref "L1") (pin "2") (pinfunction "2_2") (pintype "passive"))
      (node (ref "MIDI_OUT") (pin "5") (pinfunction "5_5") (pintype "passive"))
    )
    (net (code "61") (name "Net-(L2-Pad2)") (class "Default")
      (node (ref "L2") (pin "2") (pinfunction "2_2") (pintype "passive"))
      (node (ref "MIDI_IN") (pin "5") (pinfunction "5_5") (pintype "passive"))
    )
    (net (code "62") (name "Net-(L3-Pad1)") (class "Default")
      (node (ref "L3") (pin "1") (pinfunction "1_1") (pintype "passive"))
      (node (ref "MIDI_IN") (pin "4") (pinfunction "4_4") (pintype "passive"))
    )
    (net (code "63") (name "Net-(L3-Pad2)") (class "Default")
      (node (ref "L3") (pin "2") (pinfunction "2_2") (pintype "passive"))
      (node (ref "R12") (pin "2") (pinfunction "2_2") (pintype "passive"))
    )
    (net (code "64") (name "Net-(L4-Pad1)") (class "Default")
      (node (ref "L4") (pin "1") (pinfunction "1_1") (pintype "passive"))
      (node (ref "MIDI_OUT") (pin "4") (pinfunction "4_4") (pintype "passive"))
    )
    (net (code "65") (name "Net-(L4-Pad2)") (class "Default")
      (node (ref "L4") (pin "2") (pinfunction "2_2") (pintype "passive"))
      (node (ref "R13") (pin "2") (pinfunction "2_2") (pintype "passive"))
    )
    (net (code "66") (name "Net-(LED1-PadA)") (class "Default")
      (node (ref "LED1") (pin "A") (pinfunction "A_A") (pintype "passive"))
      (node (ref "R7") (pin "1") (pinfunction "1_1") (pintype "passive"))
    )
    (net (code "67") (name "Net-(LED2-PadA)") (class "Default")
      (node (ref "LED2") (pin "A") (pinfunction "A_A") (pintype "passive"))
      (node (ref "R8") (pin "1") (pinfunction "1_1") (pintype "passive"))
    )
    (net (code "68") (name "Net-(OSC1-OUT)") (class "Default")
      (node (ref "OSC1") (pin "3") (pinfunction "OUT_3") (pintype "output"))
      (node (ref "R48") (pin "1") (pinfunction "1_1") (pintype "passive"))
    )
    (net (code "69") (name "Net-(U2B-IO1)") (class "Default")
      (node (ref "R1") (pin "1") (pinfunction "1_1") (pintype "passive"))
      (node (ref "U2") (pin "2") (pinfunction "IO1_2") (pintype "bidirectional"))
      (node (ref "USB") (pin "3") (pinfunction "3_3") (pintype "bidirectional"))
    )
    (net (code "70") (name "Net-(U2B-IO2)") (class "Default")
      (node (ref "R2") (pin "1") (pinfunction "1_1") (pintype "passive"))
      (node (ref "U2") (pin "3") (pinfunction "IO2_3") (pintype "bidirectional"))
      (node (ref "USB") (pin "2") (pinfunction "2_2") (pintype "bidirectional"))
    )
    (net (code "71") (name "unconnected-(IC1-JTDI-Pad77)") (class "Default")
      (node (ref "IC1") (pin "77") (pinfunction "JTDI_77") (pintype "input"))
    )
    (net (code "72") (name "unconnected-(IC1-JTDO-Pad89)") (class "Default")
      (node (ref "IC1") (pin "89") (pinfunction "JTDO_89") (pintype "output"))
    )
    (net (code "73") (name "unconnected-(IC1-JTRST-Pad90)") (class "Default")
      (node (ref "IC1") (pin "90") (pinfunction "JTRST_90") (pintype "input"))
    )
    (net (code "74") (name "unconnected-(IC1-PA1-Pad24)") (class "Default")
      (node (ref "IC1") (pin "24") (pinfunction "PA1_24") (pintype "bidirectional"))
    )
    (net (code "75") (name "unconnected-(IC1-PA3-Pad26)") (class "Default")
      (node (ref "IC1") (pin "26") (pinfunction "PA3_26") (pintype "bidirectional"))
    )
    (net (code "76") (name "unconnected-(IC1-PA4-Pad29)") (class "Default")
      (node (ref "IC1") (pin "29") (pinfunction "PA4_29") (pintype "bidirectional"))
    )
    (net (code "77") (name "unconnected-(IC1-PA6-Pad31)") (class "Default")
      (node (ref "IC1") (pin "31") (pinfunction "PA6_31") (pintype "bidirectional"))
    )
    (net (code "78") (name "unconnected-(IC1-PA8-Pad67)") (class "Default")
      (node (ref "IC1") (pin "67") (pinfunction "PA8_67") (pintype "bidirectional"))
    )
    (net (code "79") (name "unconnected-(IC1-PA9-Pad68)") (class "Default")
      (node (ref "IC1") (pin "68") (pinfunction "PA9_68") (pintype "bidirectional"))
    )
    (net (code "80") (name "unconnected-(IC1-PA10-Pad69)") (class "Default")
      (node (ref "IC1") (pin "69") (pinfunction "PA10_69") (pintype "bidirectional"))
    )
    (net (code "81") (name "unconnected-(IC1-PA11-Pad70)") (class "Default")
      (node (ref "IC1") (pin "70") (pinfunction "PA11_70") (pintype "bidirectional"))
    )
    (net (code "82") (name "unconnected-(IC1-PA12-Pad71)") (class "Default")
      (node (ref "IC1") (pin "71") (pinfunction "PA12_71") (pintype "bidirectional"))
    )
    (net (code "83") (name "unconnected-(IC1-PB5-Pad91)") (class "Default")
      (node (ref "IC1") (pin "91") (pinfunction "PB5_91") (pintype "bidirectional"))
    )
    (net (code "84") (name "unconnected-(IC1-PB6-Pad92)") (class "Default")
      (node (ref "IC1") (pin "92") (pinfunction "PB6_92") (pintype "bidirectional"))
    )
    (net (code "85") (name "unconnected-(IC1-PB7-Pad93)") (class "Default")
      (node (ref "IC1") (pin "93") (pinfunction "PB7_93") (pintype "bidirectional"))
    )
    (net (code "86") (name "unconnected-(IC1-PB8-Pad95)") (class "Default")
      (node (ref "IC1") (pin "95") (pinfunction "PB8_95") (pintype "bidirectional"))
    )
    (net (code "87") (name "unconnected-(IC1-PB9-Pad96)") (class "Default")
      (node (ref "IC1") (pin "96") (pinfunction "PB9_96") (pintype "bidirectional"))
    )
    (net (code "88") (name "unconnected-(IC1-PB10-Pad47)") (class "Default")
      (node (ref "IC1") (pin "47") (pinfunction "PB10_47") (pintype "bidirectional"))
    )
    (net (code "89") (name "unconnected-(IC1-PB11-Pad48)") (class "Default")
      (node (ref "IC1") (pin "48") (pinfunction "PB11_48") (pintype "bidirectional"))
    )
    (net (code "90") (name "unconnected-(IC1-PB12-Pad51)") (class "Default")
      (node (ref "IC1") (pin "51") (pinfunction "PB12_51") (pintype "bidirectional"))
    )
    (net (code "91") (name "unconnected-(IC1-PC0-Pad15)") (class "Default")
      (node (ref "IC1") (pin "15") (pinfunction "PC0_15") (pintype "bidirectional"))
    )
    (net (code "92") (name "unconnected-(IC1-PC1-Pad16)") (class "Default")
      (node (ref "IC1") (pin "16") (pinfunction "PC1_16") (pintype "bidirectional"))
    )
    (net (code "93") (name "unconnected-(IC1-PC2-Pad17)") (class "Default")
      (node (ref "IC1") (pin "17") (pinfunction "PC2_17") (pintype "bidirectional"))
    )
    (net (code "94") (name "unconnected-(IC1-PC3-Pad18)") (class "Default")
      (node (ref "IC1") (pin "18") (pinfunction "PC3_18") (pintype "bidirectional"))
    )
    (net (code "95") (name "unconnected-(IC1-PC8-Pad65)") (class "Default")
      (node (ref "IC1") (pin "65") (pinfunction "PC8_65") (pintype "bidirectional"))
    )
    (net (code "96") (name "unconnected-(IC1-PC13-Pad7)") (class "Default")
      (node (ref "IC1") (pin "7") (pinfunction "PC13_7") (pintype "bidirectional"))
    )
    (net (code "97") (name "unconnected-(IC1-PC14-Pad8)") (class "Default")
      (node (ref "IC1") (pin "8") (pinfunction "PC14_8") (pintype "bidirectional"))
    )
    (net (code "98") (name "unconnected-(IC1-PC15-Pad9)") (class "Default")
      (node (ref "IC1") (pin "9") (pinfunction "PC15_9") (pintype "bidirectional"))
    )
    (net (code "99") (name "unconnected-(IC1-PD2-Pad83)") (class "Default")
      (node (ref "IC1") (pin "83") (pinfunction "PD2_83") (pintype "bidirectional"))
    )
    (net (code "100") (name "unconnected-(IC1-PD7-Pad88)") (class "Default")
      (node (ref "IC1") (pin "88") (pinfunction "PD7_88") (pintype "bidirectional"))
    )
    (net (code "101") (name "unconnected-(IC1-PD8-Pad55)") (class "Default")
      (node (ref "IC1") (pin "55") (pinfunction "PD8_55") (pintype "bidirectional"))
    )
    (net (code "102") (name "unconnected-(IC1-PD9-Pad56)") (class "Default")
      (node (ref "IC1") (pin "56") (pinfunction "PD9_56") (pintype "bidirectional"))
    )
    (net (code "103") (name "unconnected-(IC1-PD10-Pad57)") (class "Default")
      (node (ref "IC1") (pin "57") (pinfunction "PD10_57") (pintype "bidirectional"))
    )
    (net (code "104") (name "unconnected-(IC1-PD11-Pad58)") (class "Default")
      (node (ref "IC1") (pin "58") (pinfunction "PD11_58") (pintype "bidirectional"))
    )
    (net (code "105") (name "unconnected-(IC1-PD12-Pad59)") (class "Default")
      (node (ref "IC1") (pin "59") (pinfunction "PD12_59") (pintype "bidirectional"))
    )
    (net (code "106") (name "unconnected-(IC1-PD13-Pad60)") (class "Default")
      (node (ref "IC1") (pin "60") (pinfunction "PD13_60") (pintype "bidirectional"))
    )
    (net (code "107") (name "unconnected-(IC1-PD14-Pad61)") (class "Default")
      (node (ref "IC1") (pin "61") (pinfunction "PD14_61") (pintype "bidirectional"))
    )
    (net (code "108") (name "unconnected-(IC1-PD15-Pad62)") (class "Default")
      (node (ref "IC1") (pin "62") (pinfunction "PD15_62") (pintype "bidirectional"))
    )
    (net (code "109") (name "unconnected-(IC1-PE0-Pad97)") (class "Default")
      (node (ref "IC1") (pin "97") (pinfunction "PE0_97") (pintype "bidirectional"))
    )
    (net (code "110") (name "unconnected-(IC1-PE1-Pad98)") (class "Default")
      (node (ref "IC1") (pin "98") (pinfunction "PE1_98") (pintype "bidirectional"))
    )
    (net (code "111") (name "unconnected-(IC1-PE15-Pad46)") (class "Default")
      (node (ref "IC1") (pin "46") (pinfunction "PE15_46") (pintype "bidirectional"))
    )
    (net (code "112") (name "unconnected-(MIDI_IN-Pad1)") (class "Default")
      (node (ref "MIDI_IN") (pin "1") (pinfunction "1_1") (pintype "passive"))
    )
    (net (code "113") (name "unconnected-(MIDI_IN-Pad3)") (class "Default")
      (node (ref "MIDI_IN") (pin "3") (pinfunction "3_3") (pintype "passive"))
    )
    (net (code "114") (name "unconnected-(MIDI_OUT-Pad1)") (class "Default")
      (node (ref "MIDI_OUT") (pin "1") (pinfunction "1_1") (pintype "passive"))
    )
    (net (code "115") (name "unconnected-(MIDI_OUT-Pad3)") (class "Default")
      (node (ref "MIDI_OUT") (pin "3") (pinfunction "3_3") (pintype "passive"))
    )
    (net (code "116") (name "unconnected-(OSC1-INH-Pad1)") (class "Default")
      (node (ref "OSC1") (pin "1") (pinfunction "INH_1") (pintype "bidirectional"))
    )
    (net (code "117") (name "unconnected-(TC1-Pad7)") (class "Default")
      (node (ref "TC1") (pin "7") (pinfunction "7_7") (pintype "passive"))
    )
  )
)
